# IRIS1304_v2_0.net
KiCad netlist of a schematic drawn in EAGLE
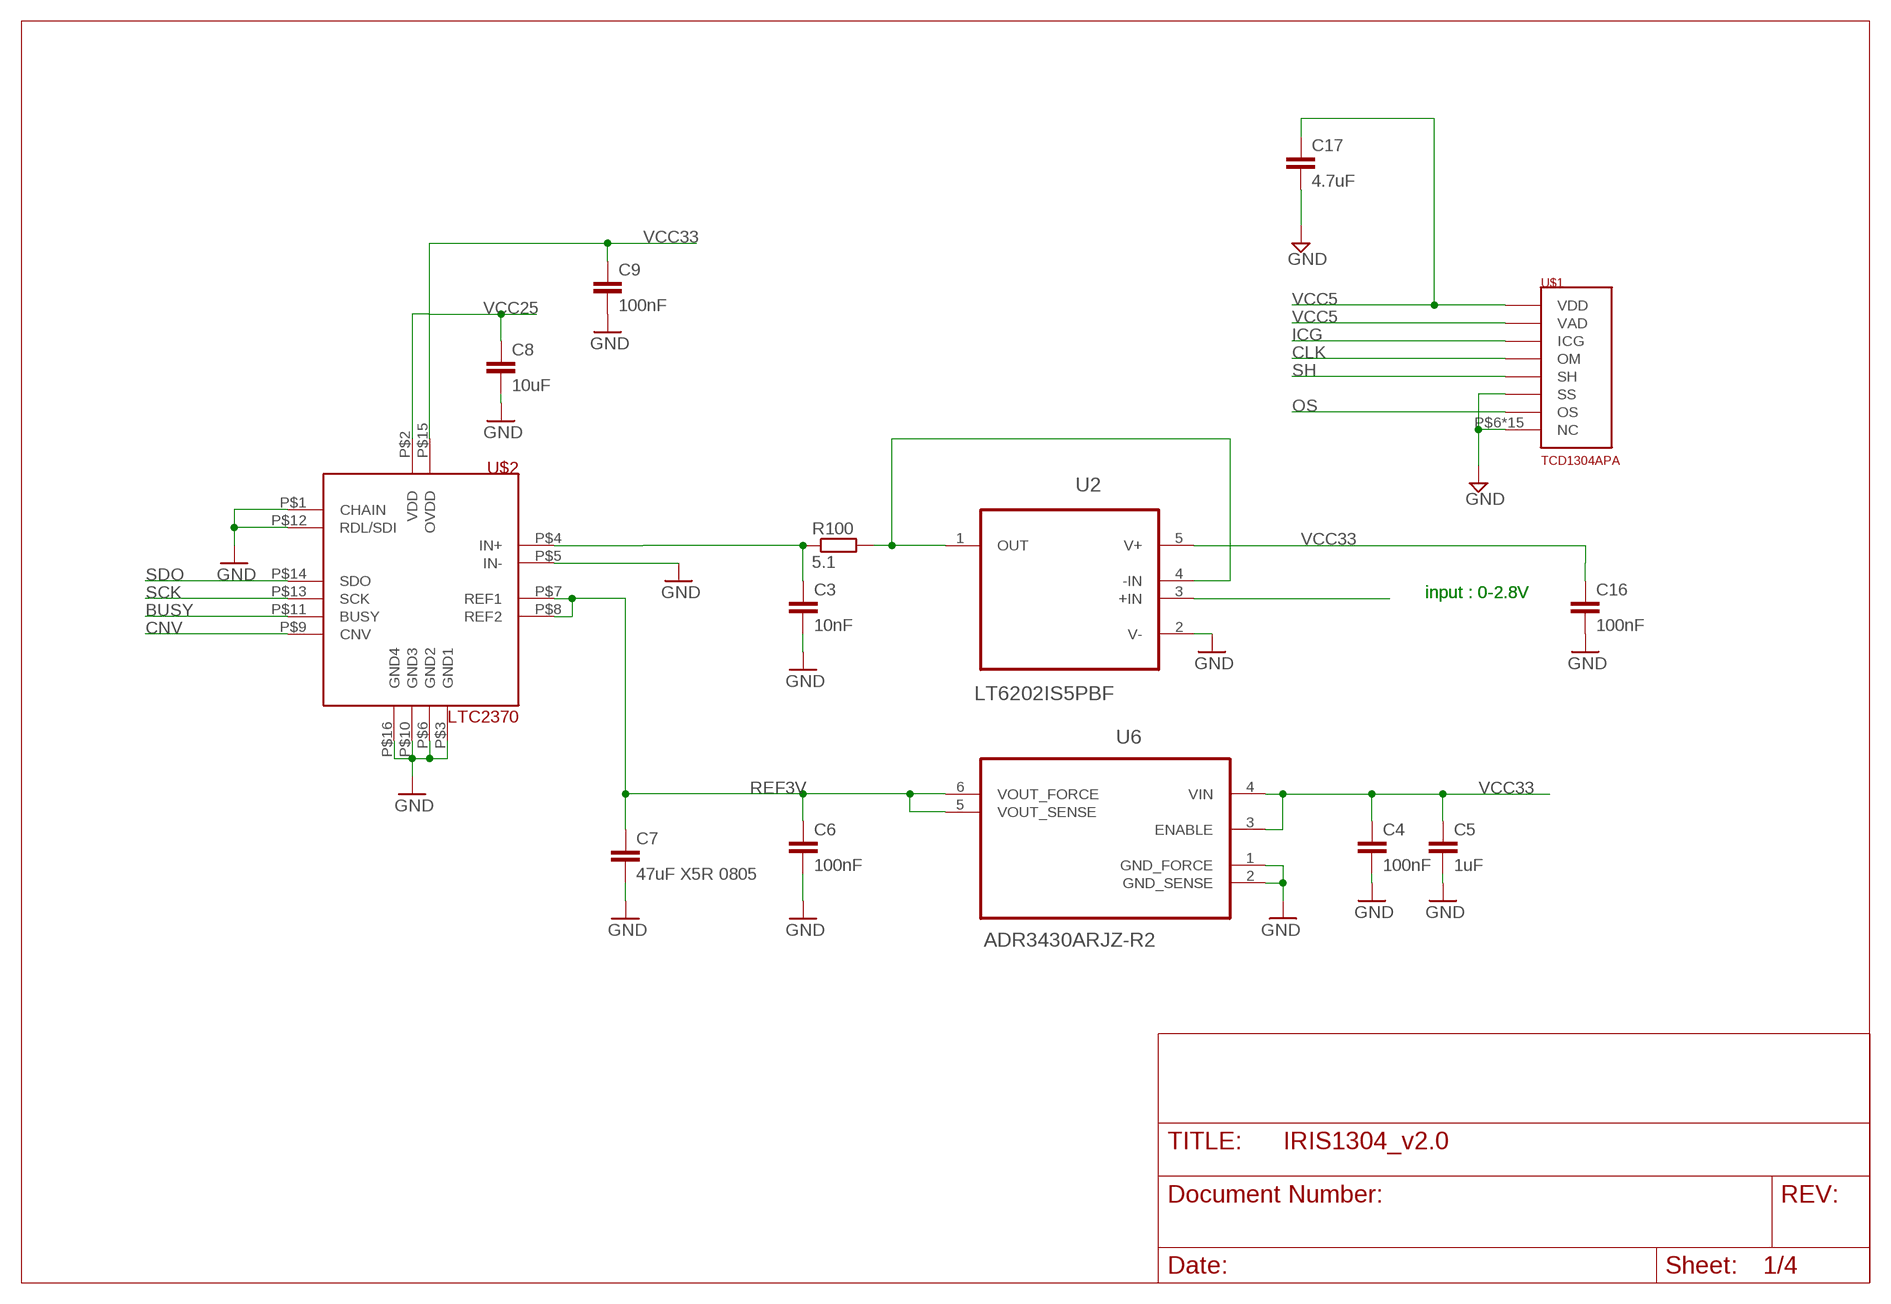
[diagram p0: schematic, sheet 1]
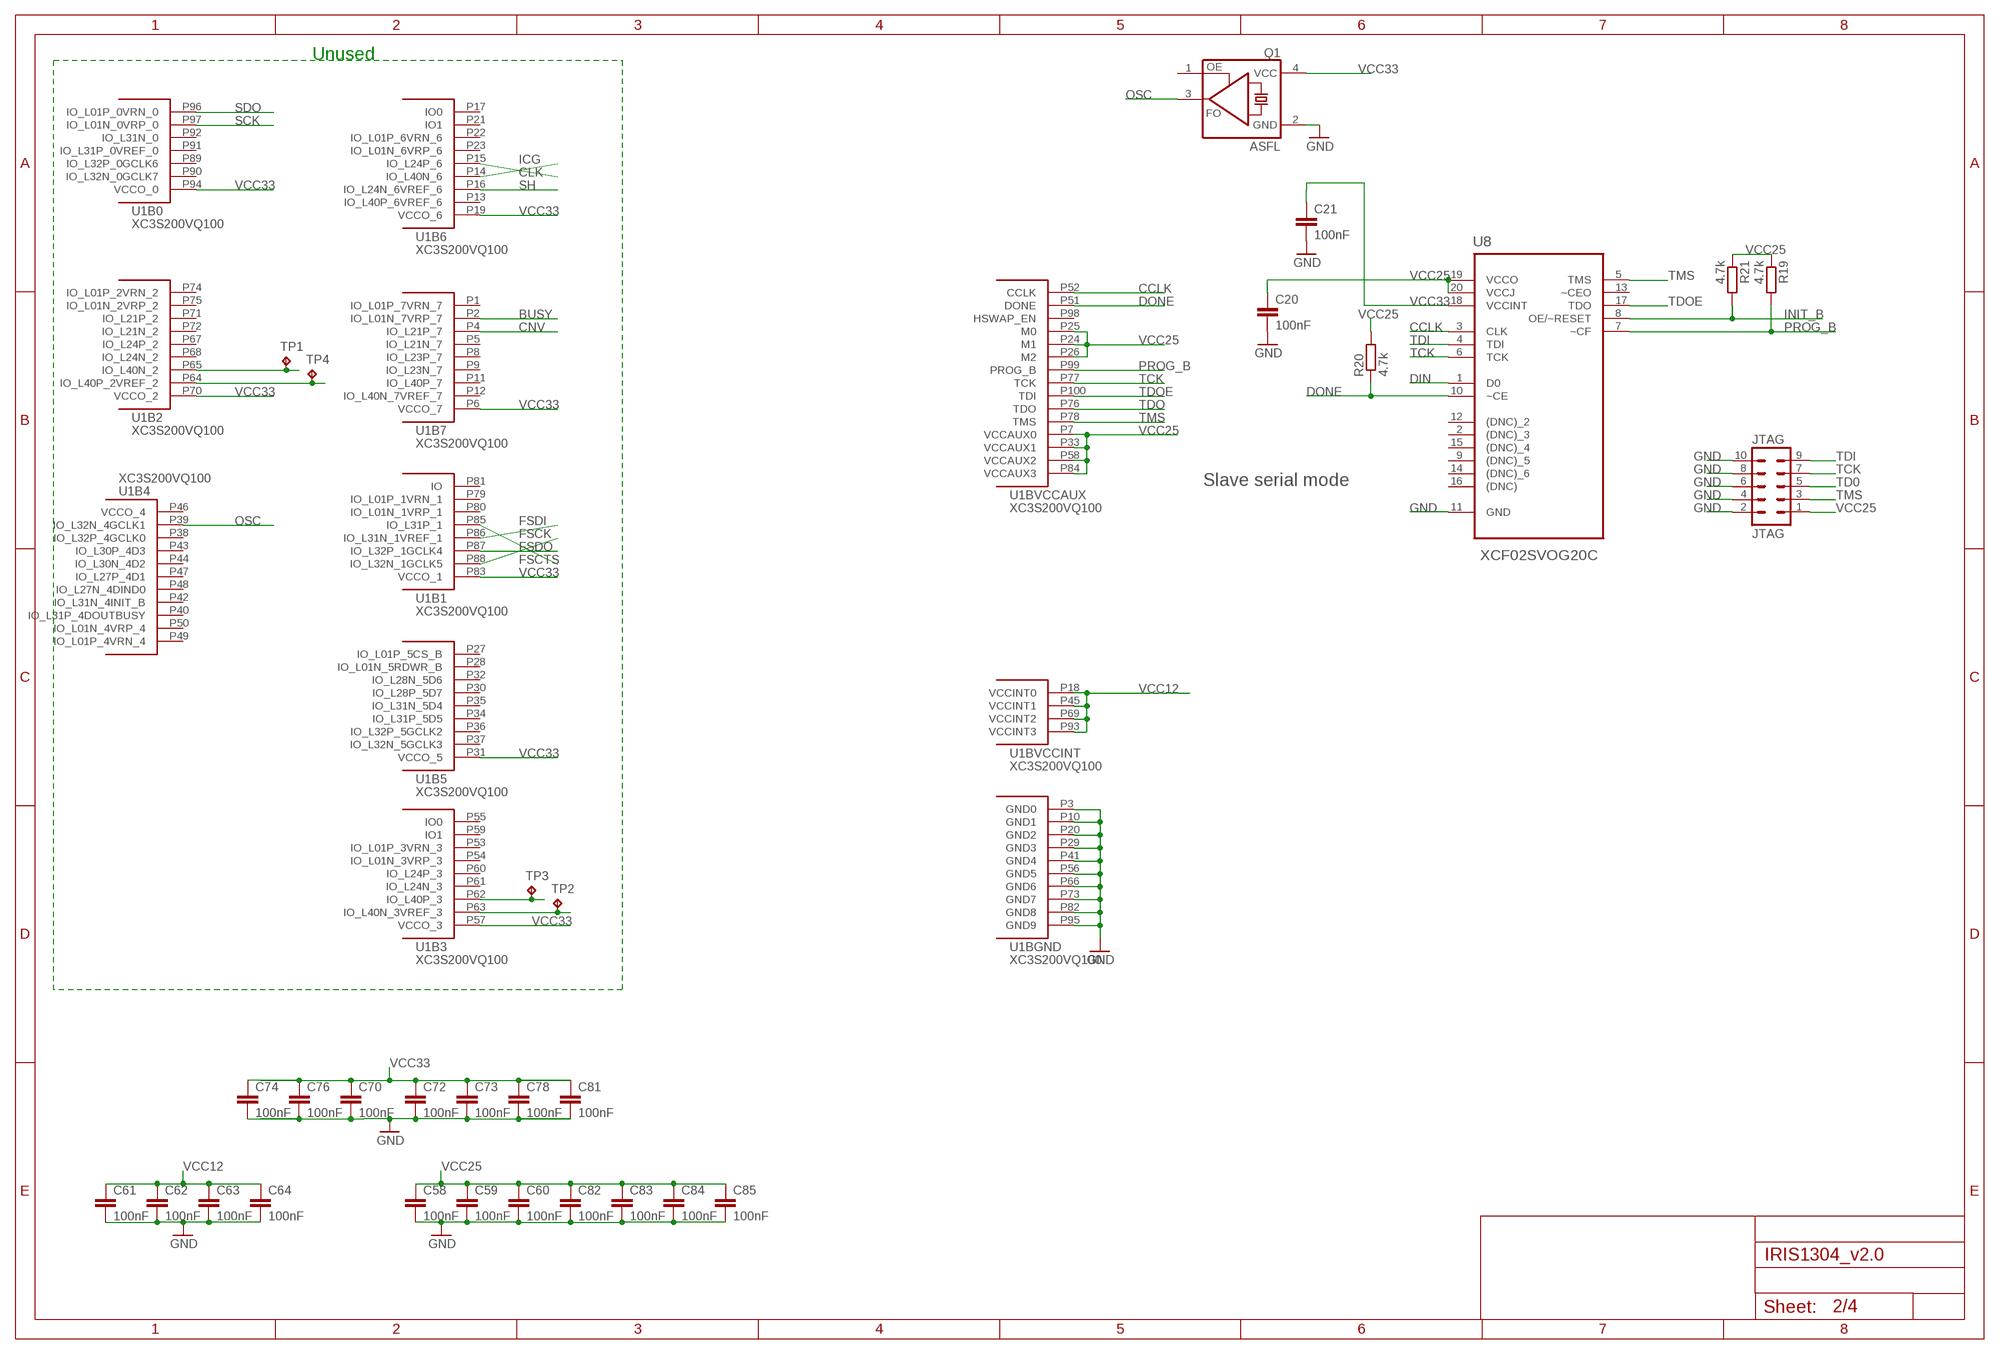
[diagram p1: schematic, sheet 2]
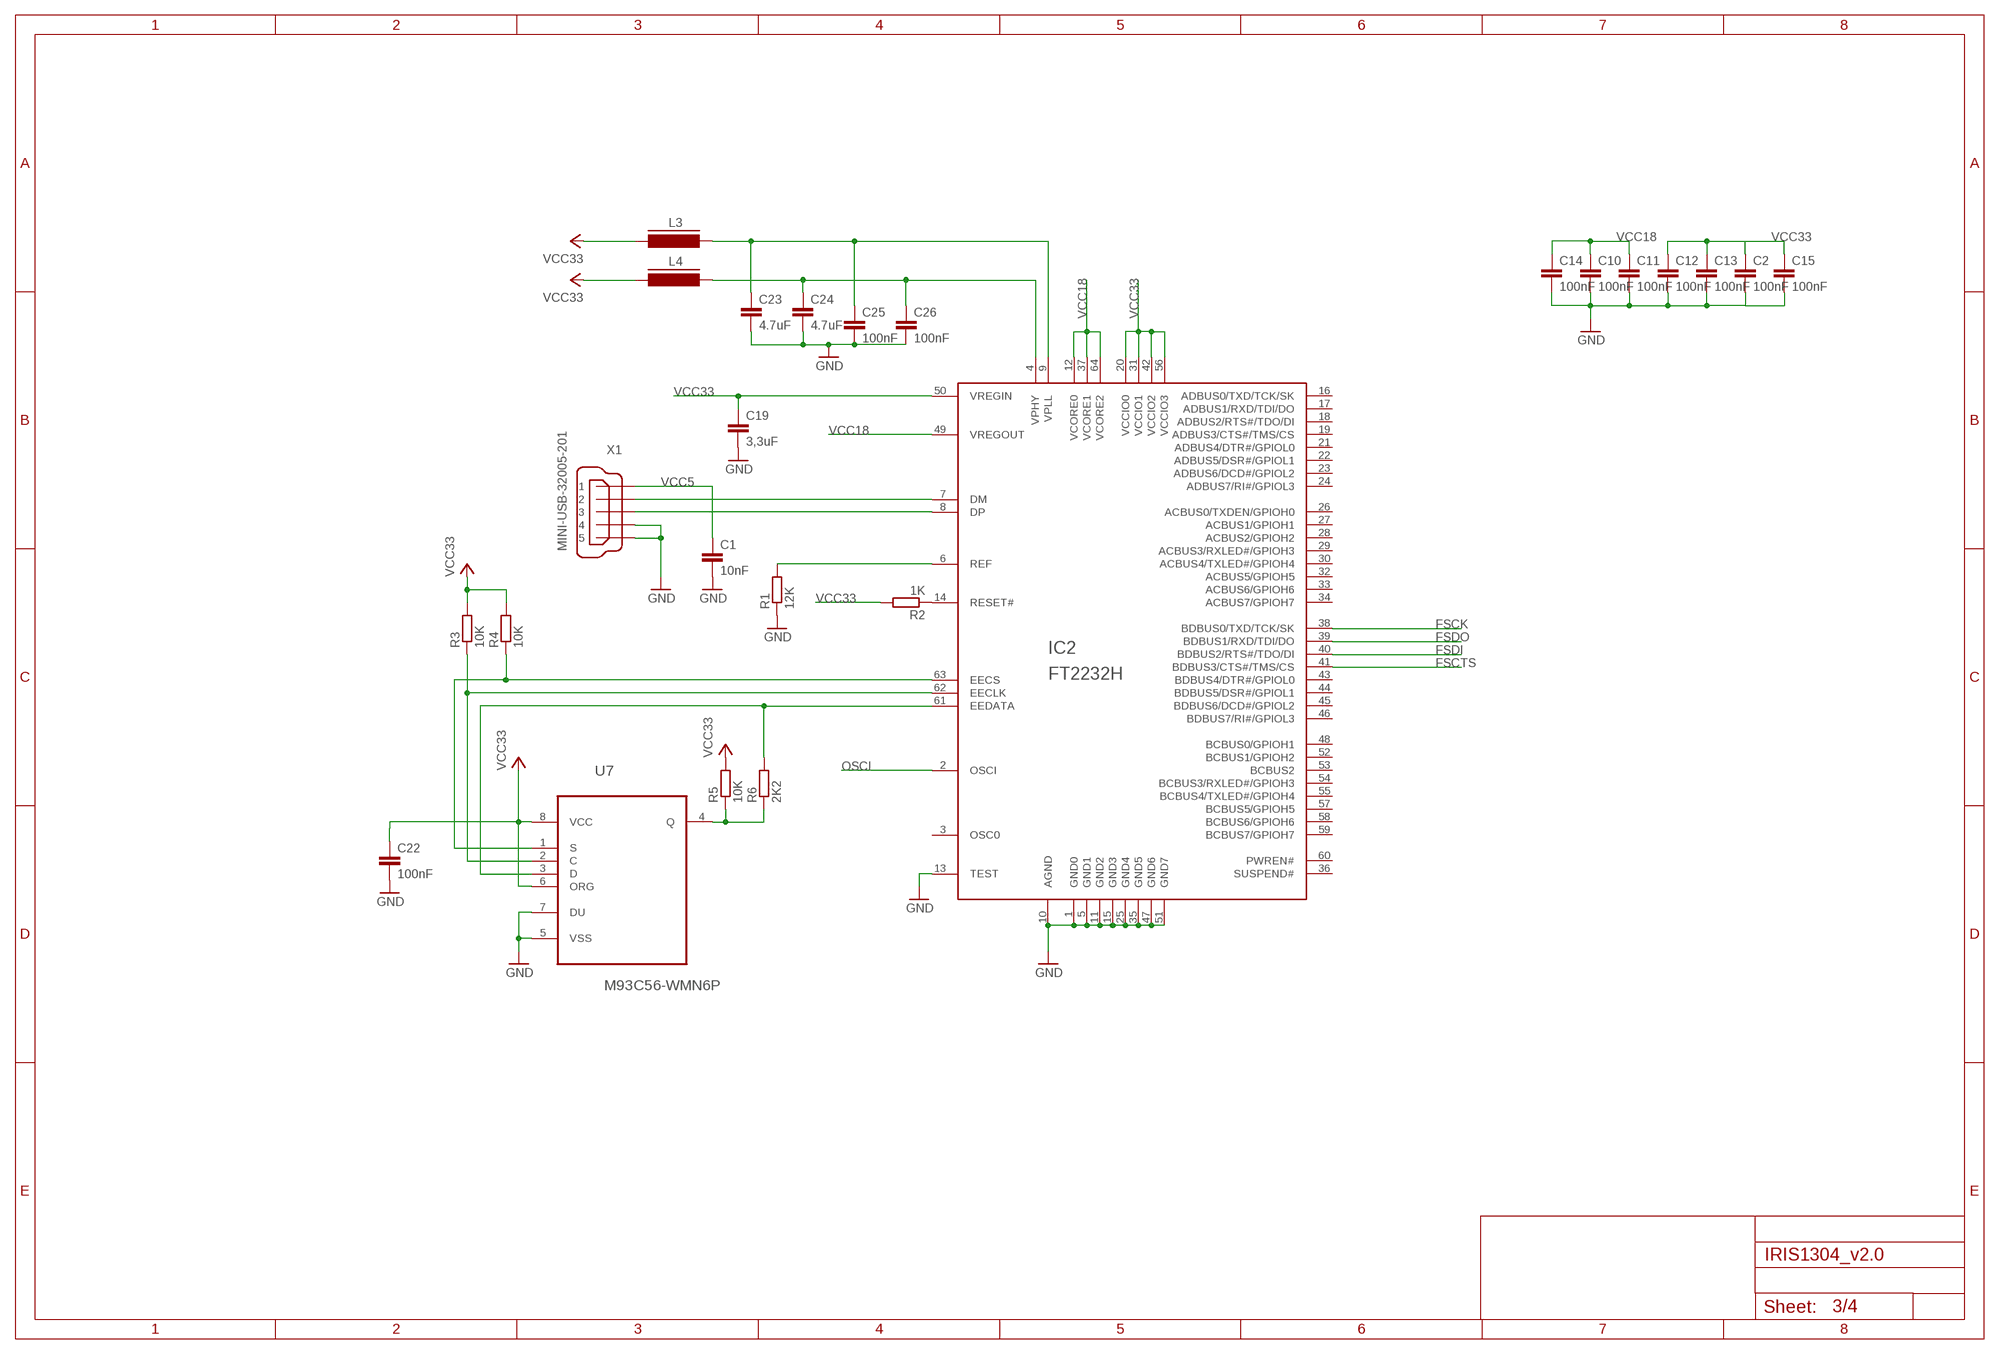
[diagram p2: schematic, sheet 3]
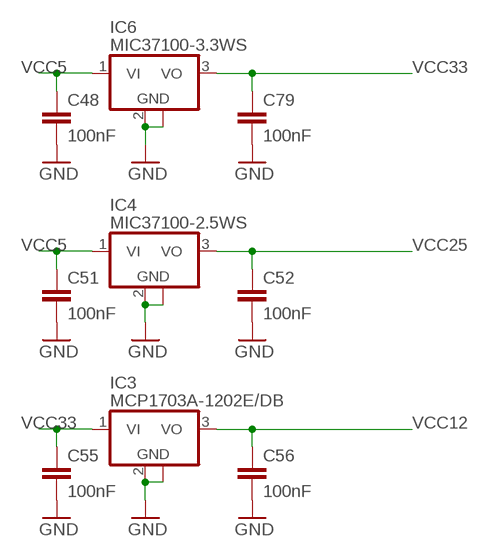
[diagram p3: schematic, sheet 4]

(export (version "E")
  (design (tool "Eeschema 10.0.6"))
  (components
    (comp (ref "C48")
      (value "100nF")
      (footprint "eagle-import:C0603")
      (fields (field (name "MF") "AVX") (field (name "MPN") "06033G104ZAT2A"))
      (libsource (lib "eagle-import") (part "C-EUC0603"))
    )
    (comp (ref "C51")
      (value "100nF")
      (footprint "eagle-import:C0603")
      (fields (field (name "MF") "AVX") (field (name "MPN") "06033G104ZAT2A"))
      (libsource (lib "eagle-import") (part "C-EUC0603"))
    )
    (comp (ref "C52")
      (value "100nF")
      (footprint "eagle-import:C0603")
      (fields (field (name "MF") "AVX") (field (name "MPN") "06033G104ZAT2A"))
      (libsource (lib "eagle-import") (part "C-EUC0603"))
    )
    (comp (ref "C55")
      (value "100nF")
      (footprint "eagle-import:C0603")
      (fields (field (name "MF") "AVX") (field (name "MPN") "06033G104ZAT2A"))
      (libsource (lib "eagle-import") (part "C-EUC0603"))
    )
    (comp (ref "C56")
      (value "100nF")
      (footprint "eagle-import:C0603")
      (fields (field (name "MF") "AVX") (field (name "MPN") "06033G104ZAT2A"))
      (libsource (lib "eagle-import") (part "C-EUC0603"))
    )
    (comp (ref "C79")
      (value "100nF")
      (footprint "eagle-import:C0603")
      (fields (field (name "MF") "AVX") (field (name "MPN") "06033G104ZAT2A"))
      (libsource (lib "eagle-import") (part "C-EUC0603"))
    )
    (comp (ref "IC3")
      (value "MCP1703A-1202E/DB")
      (footprint "eagle-import:SOT223")
      (fields (field (name "MF") "MICROCHIP"))
      (libsource (lib "eagle-import") (part "UA78MDCY05"))
    )
    (comp (ref "IC4")
      (value "MIC37100-2.5WS")
      (footprint "eagle-import:SOT223")
      (fields (field (name "MF") "MICREL SEMICONDUCTOR") (field (name "MPN") "MIC37100-2.5WS TR"))
      (libsource (lib "eagle-import") (part "UA78MDCY05"))
    )
    (comp (ref "IC6")
      (value "MIC37100-3.3WS")
      (footprint "eagle-import:SOT223")
      (fields (field (name "MF") "MICREL SEMICONDUCTOR"))
      (libsource (lib "eagle-import") (part "UA78MDCY05"))
    )
    (comp (ref "C20")
      (value "100nF")
      (footprint "eagle-import:C0603")
      (fields (field (name "MF") "AVX") (field (name "MPN") "06033G104ZAT2A"))
      (libsource (lib "eagle-import") (part "C-EUC0603"))
    )
    (comp (ref "C21")
      (value "100nF")
      (footprint "eagle-import:C0603")
      (fields (field (name "MF") "AVX") (field (name "MPN") "06033G104ZAT2A"))
      (libsource (lib "eagle-import") (part "C-EUC0603"))
    )
    (comp (ref "C58")
      (value "100nF")
      (footprint "eagle-import:C0603")
      (fields (field (name "MF") "AVX") (field (name "MPN") "06033G104ZAT2A"))
      (libsource (lib "eagle-import") (part "C-EUC0603"))
    )
    (comp (ref "C59")
      (value "100nF")
      (footprint "eagle-import:C0603")
      (fields (field (name "MF") "AVX") (field (name "MPN") "06033G104ZAT2A"))
      (libsource (lib "eagle-import") (part "C-EUC0603"))
    )
    (comp (ref "C60")
      (value "100nF")
      (footprint "eagle-import:C0603")
      (fields (field (name "MF") "AVX") (field (name "MPN") "06033G104ZAT2A"))
      (libsource (lib "eagle-import") (part "C-EUC0603"))
    )
    (comp (ref "C61")
      (value "100nF")
      (footprint "eagle-import:C0603")
      (fields (field (name "MF") "AVX") (field (name "MPN") "06033G104ZAT2A"))
      (libsource (lib "eagle-import") (part "C-EUC0603"))
    )
    (comp (ref "C62")
      (value "100nF")
      (footprint "eagle-import:C0603")
      (fields (field (name "MF") "AVX") (field (name "MPN") "06033G104ZAT2A"))
      (libsource (lib "eagle-import") (part "C-EUC0603"))
    )
    (comp (ref "C63")
      (value "100nF")
      (footprint "eagle-import:C0603")
      (fields (field (name "MF") "AVX") (field (name "MPN") "06033G104ZAT2A"))
      (libsource (lib "eagle-import") (part "C-EUC0603"))
    )
    (comp (ref "C64")
      (value "100nF")
      (footprint "eagle-import:C0603")
      (fields (field (name "MF") "AVX") (field (name "MPN") "06033G104ZAT2A"))
      (libsource (lib "eagle-import") (part "C-EUC0603"))
    )
    (comp (ref "C70")
      (value "100nF")
      (footprint "eagle-import:C0603")
      (fields (field (name "MF") "AVX") (field (name "MPN") "06033G104ZAT2A"))
      (libsource (lib "eagle-import") (part "C-EUC0603"))
    )
    (comp (ref "C72")
      (value "100nF")
      (footprint "eagle-import:C0603")
      (fields (field (name "MF") "AVX") (field (name "MPN") "06033G104ZAT2A"))
      (libsource (lib "eagle-import") (part "C-EUC0603"))
    )
    (comp (ref "C73")
      (value "100nF")
      (footprint "eagle-import:C0603")
      (fields (field (name "MF") "AVX") (field (name "MPN") "06033G104ZAT2A"))
      (libsource (lib "eagle-import") (part "C-EUC0603"))
    )
    (comp (ref "C74")
      (value "100nF")
      (footprint "eagle-import:C0603")
      (fields (field (name "MF") "AVX") (field (name "MPN") "06033G104ZAT2A"))
      (libsource (lib "eagle-import") (part "C-EUC0603"))
    )
    (comp (ref "C76")
      (value "100nF")
      (footprint "eagle-import:C0603")
      (fields (field (name "MF") "AVX") (field (name "MPN") "06033G104ZAT2A"))
      (libsource (lib "eagle-import") (part "C-EUC0603"))
    )
    (comp (ref "C78")
      (value "100nF")
      (footprint "eagle-import:C0603")
      (fields (field (name "MF") "AVX") (field (name "MPN") "06033G104ZAT2A"))
      (libsource (lib "eagle-import") (part "C-EUC0603"))
    )
    (comp (ref "C81")
      (value "100nF")
      (footprint "eagle-import:C0603")
      (fields (field (name "MF") "AVX") (field (name "MPN") "06033G104ZAT2A"))
      (libsource (lib "eagle-import") (part "C-EUC0603"))
    )
    (comp (ref "C82")
      (value "100nF")
      (footprint "eagle-import:C0603")
      (fields (field (name "MF") "AVX") (field (name "MPN") "06033G104ZAT2A"))
      (libsource (lib "eagle-import") (part "C-EUC0603"))
    )
    (comp (ref "C83")
      (value "100nF")
      (footprint "eagle-import:C0603")
      (fields (field (name "MF") "AVX") (field (name "MPN") "06033G104ZAT2A"))
      (libsource (lib "eagle-import") (part "C-EUC0603"))
    )
    (comp (ref "C84")
      (value "100nF")
      (footprint "eagle-import:C0603")
      (fields (field (name "MF") "AVX") (field (name "MPN") "06033G104ZAT2A"))
      (libsource (lib "eagle-import") (part "C-EUC0603"))
    )
    (comp (ref "C85")
      (value "100nF")
      (footprint "eagle-import:C0603")
      (fields (field (name "MF") "AVX") (field (name "MPN") "06033G104ZAT2A"))
      (libsource (lib "eagle-import") (part "C-EUC0603"))
    )
    (comp (ref "JTAG")
      (value "JTAG")
      (footprint "eagle-import:ML10")
      (fields
        (field (name "MF") "SAMTEC")
        (field (name "MPN") "TFML-105-01-S-D-RA")
        (field (name "OC_FARNELL") "1801377")
      )
      (libsource (lib "eagle-import") (part "ML10"))
    )
    (comp (ref "Q1")
      (value "ASFL")
      (footprint "eagle-import:ASF")
      (fields
        (field (name "MPN") "ASFLM1-50.000MHZ-C-T")
        (field (name "MF") "ABRACON")
        (field (name "MPN_1") "ASFL1-12.000MHZ-EK-T")
        (field (name "OC_FARNELL") "7943088")
      )
      (libsource (lib "eagle-import") (part "ASFL"))
    )
    (comp (ref "R19")
      (value "4.7k")
      (footprint "eagle-import:R0603")
      (fields (field (name "MF") "VISHAY DRALORIC") (field (name "MPN") "CRCW06034K70FKEA"))
      (libsource (lib "eagle-import") (part "R-EU_R0603"))
    )
    (comp (ref "R20")
      (value "4.7k")
      (footprint "eagle-import:R0603")
      (fields (field (name "MF") "VISHAY DRALORIC") (field (name "MPN") "CRCW06034K70FKEA"))
      (libsource (lib "eagle-import") (part "R-EU_R0603"))
    )
    (comp (ref "R21")
      (value "4.7k")
      (footprint "eagle-import:R0603")
      (fields (field (name "MF") "VISHAY DRALORIC") (field (name "MPN") "CRCW06034K70FKEA"))
      (libsource (lib "eagle-import") (part "R-EU_R0603"))
    )
    (comp (ref "TP1")
      (value "TPB1,27")
      (footprint "eagle-import:B1,27")
      (libsource (lib "eagle-import") (part "TPB1,27"))
    )
    (comp (ref "TP2")
      (value "TPB1,27")
      (footprint "eagle-import:B1,27")
      (libsource (lib "eagle-import") (part "TPB1,27"))
    )
    (comp (ref "TP3")
      (value "TPB1,27")
      (footprint "eagle-import:B1,27")
      (libsource (lib "eagle-import") (part "TPB1,27"))
    )
    (comp (ref "TP4")
      (value "TPB1,27")
      (footprint "eagle-import:B1,27")
      (libsource (lib "eagle-import") (part "TPB1,27"))
    )
    (comp (ref "U1")
      (value "XC3S200VQ100")
      (footprint "eagle-import:VQ100")
      (fields
        (field (name "MF") "XILINX")
        (field (name "MPN") "XC3S200A-4VQG100C")
        (field (name "OC_FARNELL") "1876204")
      )
      (libsource (lib "eagle-import") (part "XC3S200VQ100"))
    )
    (comp (ref "U8")
      (value "XCF02SVOG20C")
      (footprint "eagle-import:SOP65P640X119-20N")
      (fields (field (name "MF") "XILINX"))
      (libsource (lib "eagle-import") (part "XCF02SVOG20C"))
    )
    (comp (ref "C3")
      (value "10nF")
      (footprint "eagle-import:C0603")
      (fields (field (name "MF") "AVX") (field (name "MPN") "06035G103ZAT2A"))
      (libsource (lib "eagle-import") (part "C-EUC0603"))
    )
    (comp (ref "C4")
      (value "100nF")
      (footprint "eagle-import:C0603")
      (fields (field (name "MF") "AVX") (field (name "MPN") "06033G104ZAT2A"))
      (libsource (lib "eagle-import") (part "C-EUC0603"))
    )
    (comp (ref "C5")
      (value "1uF")
      (footprint "eagle-import:C0603")
      (fields (field (name "MF") "KEMET") (field (name "MPN") "C0603C105K3PACTU"))
      (libsource (lib "eagle-import") (part "C-EUC0603"))
    )
    (comp (ref "C6")
      (value "100nF")
      (footprint "eagle-import:C0603")
      (fields (field (name "MF") "AVX") (field (name "MPN") "06033G104ZAT2A"))
      (libsource (lib "eagle-import") (part "C-EUC0603"))
    )
    (comp (ref "C7")
      (value "47uF X5R 0805")
      (footprint "eagle-import:C0805")
      (fields (field (name "MF") "KEMET") (field (name "MPN") "C0805C476M9PACTU"))
      (libsource (lib "eagle-import") (part "C-EUC0805"))
    )
    (comp (ref "C8")
      (value "10uF")
      (footprint "eagle-import:C0603")
      (fields (field (name "MF") "KEMET") (field (name "MPN") "C0603C106M9PACTU"))
      (libsource (lib "eagle-import") (part "C-EUC0603"))
    )
    (comp (ref "C9")
      (value "100nF")
      (footprint "eagle-import:C0603")
      (fields (field (name "MF") "AVX") (field (name "MPN") "06033G104ZAT2A"))
      (libsource (lib "eagle-import") (part "C-EUC0603"))
    )
    (comp (ref "C16")
      (value "100nF")
      (footprint "eagle-import:C0603")
      (fields (field (name "MF") "AVX") (field (name "MPN") "06033G104ZAT2A"))
      (libsource (lib "eagle-import") (part "C-EUC0603"))
    )
    (comp (ref "C17")
      (value "4.7uF")
      (footprint "eagle-import:C0603")
      (fields (field (name "MF") "YAGEO (PHYCOMP)") (field (name "MPN") "CC0603KRX5R6BB475"))
      (libsource (lib "eagle-import") (part "C-EUC0603"))
    )
    (comp (ref "R100")
      (value "5.1")
      (footprint "eagle-import:R0603")
      (fields (field (name "MF") "VISHAY DALE") (field (name "MPN") "CRCW06035R10FNEA"))
      (libsource (lib "eagle-import") (part "R-EU_R0603"))
    )
    (comp (ref "U$1")
      (value "TCD1304APA")
      (footprint "eagle-import:ILX511")
      (libsource (lib "eagle-import") (part "TCD1304APA"))
    )
    (comp (ref "U$2")
      (value "LTC2370")
      (footprint "eagle-import:MSOP-16")
      (fields (field (name "MF") "LINEAR TECHNOLOGY") (field (name "MPN") "LTC2370CMS-16"))
      (libsource (lib "eagle-import") (part "LTC2370"))
    )
    (comp (ref "U2")
      (value "LT6202IS5PBF")
      (footprint "eagle-import:SOT95P280X100-5N")
      (fields (field (name "MPN") "LT6202IS5#PBF") (field (name "MF") "LINEAR TECHNOLOGY"))
      (libsource (lib "eagle-import") (part "LT6202IS5PBF"))
    )
    (comp (ref "U6")
      (value "ADR3430ARJZ-R2")
      (footprint "eagle-import:SOT95P280X145-6N")
      (fields (field (name "MF") "ANALOG DEVICES"))
      (libsource (lib "eagle-import") (part "ADR3430ARJZ-R2"))
    )
    (comp (ref "C1")
      (value "10nF")
      (footprint "eagle-import:C0603")
      (fields (field (name "MF") "AVX") (field (name "MPN") "06035G103ZAT2A"))
      (libsource (lib "eagle-import") (part "C-EUC0603"))
    )
    (comp (ref "C2")
      (value "100nF")
      (footprint "eagle-import:C0603")
      (fields (field (name "MF") "AVX") (field (name "MPN") "06033G104ZAT2A"))
      (libsource (lib "eagle-import") (part "C-EUC0603"))
    )
    (comp (ref "C10")
      (value "100nF")
      (footprint "eagle-import:C0603")
      (fields (field (name "MF") "AVX") (field (name "MPN") "06033G104ZAT2A"))
      (libsource (lib "eagle-import") (part "C-EUC0603"))
    )
    (comp (ref "C11")
      (value "100nF")
      (footprint "eagle-import:C0603")
      (fields (field (name "MF") "AVX") (field (name "MPN") "06033G104ZAT2A"))
      (libsource (lib "eagle-import") (part "C-EUC0603"))
    )
    (comp (ref "C12")
      (value "100nF")
      (footprint "eagle-import:C0603")
      (fields (field (name "MF") "AVX") (field (name "MPN") "06033G104ZAT2A"))
      (libsource (lib "eagle-import") (part "C-EUC0603"))
    )
    (comp (ref "C13")
      (value "100nF")
      (footprint "eagle-import:C0603")
      (fields (field (name "MF") "AVX") (field (name "MPN") "06033G104ZAT2A"))
      (libsource (lib "eagle-import") (part "C-EUC0603"))
    )
    (comp (ref "C14")
      (value "100nF")
      (footprint "eagle-import:C0603")
      (fields (field (name "MF") "AVX") (field (name "MPN") "06033G104ZAT2A"))
      (libsource (lib "eagle-import") (part "C-EUC0603"))
    )
    (comp (ref "C15")
      (value "100nF")
      (footprint "eagle-import:C0603")
      (fields (field (name "MF") "AVX") (field (name "MPN") "06033G104ZAT2A"))
      (libsource (lib "eagle-import") (part "C-EUC0603"))
    )
    (comp (ref "C19")
      (value "3,3uF")
      (footprint "eagle-import:C0805")
      (fields (field (name "MF") "AVX") (field (name "MPN") "0805ZD335KAT2A"))
      (libsource (lib "eagle-import") (part "C-EUC0805"))
    )
    (comp (ref "C22")
      (value "100nF")
      (footprint "eagle-import:C0603")
      (fields (field (name "MF") "AVX") (field (name "MPN") "06033G104ZAT2A"))
      (libsource (lib "eagle-import") (part "C-EUC0603"))
    )
    (comp (ref "C23")
      (value "4.7uF")
      (footprint "eagle-import:C0603")
      (fields (field (name "MF") "YAGEO (PHYCOMP)") (field (name "MPN") "CC0603KRX5R6BB475"))
      (libsource (lib "eagle-import") (part "C-EUC0603"))
    )
    (comp (ref "C24")
      (value "4.7uF")
      (footprint "eagle-import:C0603")
      (fields (field (name "MF") "YAGEO (PHYCOMP)") (field (name "MPN") "CC0603KRX5R6BB475"))
      (libsource (lib "eagle-import") (part "C-EUC0603"))
    )
    (comp (ref "C25")
      (value "100nF")
      (footprint "eagle-import:C0603")
      (fields (field (name "MF") "AVX") (field (name "MPN") "06033G104ZAT2A"))
      (libsource (lib "eagle-import") (part "C-EUC0603"))
    )
    (comp (ref "C26")
      (value "100nF")
      (footprint "eagle-import:C0603")
      (fields (field (name "MF") "AVX") (field (name "MPN") "06033G104ZAT2A"))
      (libsource (lib "eagle-import") (part "C-EUC0603"))
    )
    (comp (ref "IC2")
      (value "FT2232H")
      (footprint "eagle-import:LQFP64")
      (fields (field (name "MF") "FTDI") (field (name "MPN") "FT2232HL-R"))
      (libsource (lib "eagle-import") (part "FT2232H"))
    )
    (comp (ref "L3")
      (value "FERRITE_BEAD805")
      (footprint "eagle-import:FB805")
      (libsource (lib "eagle-import") (part "FERRITE_BEAD805"))
    )
    (comp (ref "L4")
      (value "FERRITE_BEAD805")
      (footprint "eagle-import:FB805")
      (libsource (lib "eagle-import") (part "FERRITE_BEAD805"))
    )
    (comp (ref "R1")
      (value "12K")
      (footprint "eagle-import:R0603")
      (fields (field (name "MF") "TE CONNECTIVITY") (field (name "MPN") "CPF0201D12K1C1"))
      (libsource (lib "eagle-import") (part "R-EU_R0603"))
    )
    (comp (ref "R2")
      (value "1K")
      (footprint "eagle-import:R0603")
      (fields (field (name "MF") "VISHAY DRALORIC") (field (name "MPN") "CRCW06031K00FKEA"))
      (libsource (lib "eagle-import") (part "R-EU_R0603"))
    )
    (comp (ref "R3")
      (value "10K")
      (footprint "eagle-import:R0603")
      (fields (field (name "MF") "TE CONNECTIVITY / NEOHM") (field (name "MPN") "CPF0603F10KC1"))
      (libsource (lib "eagle-import") (part "R-EU_R0603"))
    )
    (comp (ref "R4")
      (value "10K")
      (footprint "eagle-import:R0603")
      (fields (field (name "MF") "TE CONNECTIVITY / NEOHM") (field (name "MPN") "CPF0603F10KC1"))
      (libsource (lib "eagle-import") (part "R-EU_R0603"))
    )
    (comp (ref "R5")
      (value "10K")
      (footprint "eagle-import:R0603")
      (fields (field (name "MF") "TE CONNECTIVITY / NEOHM") (field (name "MPN") "CPF0603F10KC1"))
      (libsource (lib "eagle-import") (part "R-EU_R0603"))
    )
    (comp (ref "R6")
      (value "2K2")
      (footprint "eagle-import:R0603")
      (fields (field (name "MF") "PANASONIC") (field (name "MPN") "ERJP03F2201V"))
      (libsource (lib "eagle-import") (part "R-EU_R0603"))
    )
    (comp (ref "U7")
      (value "M93C56-WMN6P")
      (footprint "eagle-import:SOIC127P600X175-8N")
      (fields (field (name "MF") "STMICROELECTRONICS"))
      (libsource (lib "eagle-import") (part "M93C56-WMN6P"))
    )
    (comp (ref "X1")
      (value "MINI-USB-32005-201")
      (footprint "eagle-import:32005-201")
      (fields
        (field (name "MF") "WURTH ELEKTRONIK")
        (field (name "MPN") "65100516121")
        (field (name "OC_FARNELL") "1642036")
      )
      (libsource (lib "eagle-import") (part "MINI-USB-32005-201"))
    )
  )
  (nets
    (net (code "1") (name "BUSY") (class "Default")
      (node (ref "U$2") (pin "P$11") (pinfunction "BUSY_P$11") (pintype "bidirectional"))
      (node (ref "U1") (pin "P2") (pinfunction "IO_L01N_7VRP_7_P2") (pintype "bidirectional"))
    )
    (net (code "2") (name "CCLK") (class "Default")
      (node (ref "U1") (pin "P52") (pinfunction "CCLK_P52") (pintype "bidirectional"))
      (node (ref "U8") (pin "3") (pinfunction "CLK_3") (pintype "input"))
    )
    (net (code "3") (name "CLK") (class "Default")
      (node (ref "U$1") (pin "P$4") (pinfunction "OM_P$4") (pintype "bidirectional"))
      (node (ref "U1") (pin "P15") (pinfunction "IO_L24P_6_P15") (pintype "bidirectional"))
    )
    (net (code "4") (name "CNV") (class "Default")
      (node (ref "U$2") (pin "P$9") (pinfunction "CNV_P$9") (pintype "bidirectional"))
      (node (ref "U1") (pin "P4") (pinfunction "IO_L21P_7_P4") (pintype "bidirectional"))
    )
    (net (code "5") (name "DIN") (class "Default")
      (node (ref "U8") (pin "1") (pinfunction "D0_1") (pintype "input"))
    )
    (net (code "6") (name "DONE") (class "Default")
      (node (ref "R20") (pin "1") (pinfunction "1_1") (pintype "passive"))
      (node (ref "U1") (pin "P51") (pinfunction "DONE_P51") (pintype "bidirectional"))
      (node (ref "U8") (pin "10") (pinfunction "~{CE}_10") (pintype "input"))
    )
    (net (code "7") (name "FSCK") (class "Default")
      (node (ref "IC2") (pin "38") (pinfunction "BDBUS0/TXD/TCK/SK_38") (pintype "bidirectional"))
      (node (ref "U1") (pin "P88") (pinfunction "IO_L32N_1GCLK5_P88") (pintype "bidirectional"))
    )
    (net (code "8") (name "FSCTS") (class "Default")
      (node (ref "IC2") (pin "41") (pinfunction "BDBUS3/CTS#/TMS/CS_41") (pintype "bidirectional"))
      (node (ref "U1") (pin "P85") (pinfunction "IO_L31P_1_P85") (pintype "bidirectional"))
    )
    (net (code "9") (name "FSDI") (class "Default")
      (node (ref "IC2") (pin "40") (pinfunction "BDBUS2/RTS#/TDO/DI_40") (pintype "bidirectional"))
      (node (ref "U1") (pin "P86") (pinfunction "IO_L31N_1VREF_1_P86") (pintype "bidirectional"))
    )
    (net (code "10") (name "FSDO") (class "Default")
      (node (ref "IC2") (pin "39") (pinfunction "BDBUS1/RXD/TDI/DO_39") (pintype "bidirectional"))
      (node (ref "U1") (pin "P87") (pinfunction "IO_L32P_1GCLK4_P87") (pintype "bidirectional"))
    )
    (net (code "11") (name "GND") (class "Default")
      (node (ref "C1") (pin "2") (pinfunction "2_2") (pintype "passive"))
      (node (ref "C10") (pin "2") (pinfunction "2_2") (pintype "passive"))
      (node (ref "C11") (pin "2") (pinfunction "2_2") (pintype "passive"))
      (node (ref "C12") (pin "2") (pinfunction "2_2") (pintype "passive"))
      (node (ref "C13") (pin "2") (pinfunction "2_2") (pintype "passive"))
      (node (ref "C14") (pin "2") (pinfunction "2_2") (pintype "passive"))
      (node (ref "C15") (pin "2") (pinfunction "2_2") (pintype "passive"))
      (node (ref "C16") (pin "2") (pinfunction "2_2") (pintype "passive"))
      (node (ref "C17") (pin "2") (pinfunction "2_2") (pintype "passive"))
      (node (ref "C19") (pin "2") (pinfunction "2_2") (pintype "passive"))
      (node (ref "C2") (pin "2") (pinfunction "2_2") (pintype "passive"))
      (node (ref "C20") (pin "2") (pinfunction "2_2") (pintype "passive"))
      (node (ref "C21") (pin "2") (pinfunction "2_2") (pintype "passive"))
      (node (ref "C22") (pin "2") (pinfunction "2_2") (pintype "passive"))
      (node (ref "C23") (pin "2") (pinfunction "2_2") (pintype "passive"))
      (node (ref "C24") (pin "2") (pinfunction "2_2") (pintype "passive"))
      (node (ref "C25") (pin "2") (pinfunction "2_2") (pintype "passive"))
      (node (ref "C26") (pin "2") (pinfunction "2_2") (pintype "passive"))
      (node (ref "C3") (pin "2") (pinfunction "2_2") (pintype "passive"))
      (node (ref "C4") (pin "2") (pinfunction "2_2") (pintype "passive"))
      (node (ref "C48") (pin "2") (pinfunction "2_2") (pintype "passive"))
      (node (ref "C5") (pin "2") (pinfunction "2_2") (pintype "passive"))
      (node (ref "C51") (pin "2") (pinfunction "2_2") (pintype "passive"))
      (node (ref "C52") (pin "2") (pinfunction "2_2") (pintype "passive"))
      (node (ref "C55") (pin "2") (pinfunction "2_2") (pintype "passive"))
      (node (ref "C56") (pin "2") (pinfunction "2_2") (pintype "passive"))
      (node (ref "C58") (pin "2") (pinfunction "2_2") (pintype "passive"))
      (node (ref "C59") (pin "2") (pinfunction "2_2") (pintype "passive"))
      (node (ref "C6") (pin "2") (pinfunction "2_2") (pintype "passive"))
      (node (ref "C60") (pin "2") (pinfunction "2_2") (pintype "passive"))
      (node (ref "C61") (pin "2") (pinfunction "2_2") (pintype "passive"))
      (node (ref "C62") (pin "2") (pinfunction "2_2") (pintype "passive"))
      (node (ref "C63") (pin "2") (pinfunction "2_2") (pintype "passive"))
      (node (ref "C64") (pin "2") (pinfunction "2_2") (pintype "passive"))
      (node (ref "C7") (pin "2") (pinfunction "2_2") (pintype "passive"))
      (node (ref "C70") (pin "2") (pinfunction "2_2") (pintype "passive"))
      (node (ref "C72") (pin "2") (pinfunction "2_2") (pintype "passive"))
      (node (ref "C73") (pin "2") (pinfunction "2_2") (pintype "passive"))
      (node (ref "C74") (pin "2") (pinfunction "2_2") (pintype "passive"))
      (node (ref "C76") (pin "2") (pinfunction "2_2") (pintype "passive"))
      (node (ref "C78") (pin "2") (pinfunction "2_2") (pintype "passive"))
      (node (ref "C79") (pin "2") (pinfunction "2_2") (pintype "passive"))
      (node (ref "C8") (pin "2") (pinfunction "2_2") (pintype "passive"))
      (node (ref "C81") (pin "2") (pinfunction "2_2") (pintype "passive"))
      (node (ref "C82") (pin "2") (pinfunction "2_2") (pintype "passive"))
      (node (ref "C83") (pin "2") (pinfunction "2_2") (pintype "passive"))
      (node (ref "C84") (pin "2") (pinfunction "2_2") (pintype "passive"))
      (node (ref "C85") (pin "2") (pinfunction "2_2") (pintype "passive"))
      (node (ref "C9") (pin "2") (pinfunction "2_2") (pintype "passive"))
      (node (ref "IC2") (pin "1") (pinfunction "GND0_1") (pintype "bidirectional"))
      (node (ref "IC2") (pin "10") (pinfunction "AGND_10") (pintype "bidirectional"))
      (node (ref "IC2") (pin "11") (pinfunction "GND2_11") (pintype "bidirectional"))
      (node (ref "IC2") (pin "13") (pinfunction "TEST_13") (pintype "bidirectional"))
      (node (ref "IC2") (pin "15") (pinfunction "GND3_15") (pintype "bidirectional"))
      (node (ref "IC2") (pin "25") (pinfunction "GND4_25") (pintype "bidirectional"))
      (node (ref "IC2") (pin "35") (pinfunction "GND5_35") (pintype "bidirectional"))
      (node (ref "IC2") (pin "47") (pinfunction "GND6_47") (pintype "bidirectional"))
      (node (ref "IC2") (pin "5") (pinfunction "GND1_5") (pintype "bidirectional"))
      (node (ref "IC2") (pin "51") (pinfunction "GND7_51") (pintype "bidirectional"))
      (node (ref "IC3") (pin "2") (pinfunction "GND_2") (pintype "passive"))
      (node (ref "IC3") (pin "4") (pinfunction "GND_4") (pintype "passive"))
      (node (ref "IC4") (pin "2") (pinfunction "GND_2") (pintype "passive"))
      (node (ref "IC4") (pin "4") (pinfunction "GND_4") (pintype "passive"))
      (node (ref "IC6") (pin "2") (pinfunction "GND_2") (pintype "passive"))
      (node (ref "IC6") (pin "4") (pinfunction "GND_4") (pintype "passive"))
      (node (ref "JTAG") (pin "10") (pinfunction "10_10") (pintype "passive"))
      (node (ref "JTAG") (pin "2") (pinfunction "2_2") (pintype "passive"))
      (node (ref "JTAG") (pin "4") (pinfunction "4_4") (pintype "passive"))
      (node (ref "JTAG") (pin "6") (pinfunction "6_6") (pintype "passive"))
      (node (ref "JTAG") (pin "8") (pinfunction "8_8") (pintype "passive"))
      (node (ref "Q1") (pin "2") (pinfunction "GND_2") (pintype "power_in"))
      (node (ref "R1") (pin "1") (pinfunction "1_1") (pintype "passive"))
      (node (ref "U$1") (pin "P$10") (pinfunction "NC_P$10") (pintype "bidirectional"))
      (node (ref "U$1") (pin "P$11") (pinfunction "NC_P$11") (pintype "bidirectional"))
      (node (ref "U$1") (pin "P$12") (pinfunction "NC_P$12") (pintype "bidirectional"))
      (node (ref "U$1") (pin "P$13") (pinfunction "NC_P$13") (pintype "bidirectional"))
      (node (ref "U$1") (pin "P$14") (pinfunction "NC_P$14") (pintype "bidirectional"))
      (node (ref "U$1") (pin "P$15") (pinfunction "NC_P$15") (pintype "bidirectional"))
      (node (ref "U$1") (pin "P$16") (pinfunction "NC_P$16") (pintype "bidirectional"))
      (node (ref "U$1") (pin "P$17") (pinfunction "NC_P$17") (pintype "bidirectional"))
      (node (ref "U$1") (pin "P$18") (pinfunction "NC_P$18") (pintype "bidirectional"))
      (node (ref "U$1") (pin "P$19") (pinfunction "NC_P$19") (pintype "bidirectional"))
      (node (ref "U$1") (pin "P$20") (pinfunction "NC_P$20") (pintype "bidirectional"))
      (node (ref "U$1") (pin "P$22") (pinfunction "SS_P$22") (pintype "bidirectional"))
      (node (ref "U$1") (pin "P$6") (pinfunction "NC_P$6") (pintype "bidirectional"))
      (node (ref "U$1") (pin "P$7") (pinfunction "NC_P$7") (pintype "bidirectional"))
      (node (ref "U$1") (pin "P$8") (pinfunction "NC_P$8") (pintype "bidirectional"))
      (node (ref "U$1") (pin "P$9") (pinfunction "NC_P$9") (pintype "bidirectional"))
      (node (ref "U$2") (pin "P$1") (pinfunction "CHAIN_P$1") (pintype "bidirectional"))
      (node (ref "U$2") (pin "P$10") (pinfunction "GND3_P$10") (pintype "bidirectional"))
      (node (ref "U$2") (pin "P$12") (pinfunction "RDL/SDI_P$12") (pintype "bidirectional"))
      (node (ref "U$2") (pin "P$16") (pinfunction "GND4_P$16") (pintype "bidirectional"))
      (node (ref "U$2") (pin "P$3") (pinfunction "GND1_P$3") (pintype "bidirectional"))
      (node (ref "U$2") (pin "P$5") (pinfunction "IN-_P$5") (pintype "bidirectional"))
      (node (ref "U$2") (pin "P$6") (pinfunction "GND2_P$6") (pintype "bidirectional"))
      (node (ref "U1") (pin "P10") (pinfunction "GND1_P10") (pintype "passive"))
      (node (ref "U1") (pin "P20") (pinfunction "GND2_P20") (pintype "passive"))
      (node (ref "U1") (pin "P29") (pinfunction "GND3_P29") (pintype "passive"))
      (node (ref "U1") (pin "P3") (pinfunction "GND0_P3") (pintype "passive"))
      (node (ref "U1") (pin "P41") (pinfunction "GND4_P41") (pintype "passive"))
      (node (ref "U1") (pin "P56") (pinfunction "GND5_P56") (pintype "passive"))
      (node (ref "U1") (pin "P66") (pinfunction "GND6_P66") (pintype "passive"))
      (node (ref "U1") (pin "P73") (pinfunction "GND7_P73") (pintype "passive"))
      (node (ref "U1") (pin "P82") (pinfunction "GND8_P82") (pintype "passive"))
      (node (ref "U1") (pin "P95") (pinfunction "GND9_P95") (pintype "passive"))
      (node (ref "U2") (pin "2") (pinfunction "V-_2") (pintype "power_in"))
      (node (ref "U6") (pin "1") (pinfunction "GND_FORCE_1") (pintype "passive"))
      (node (ref "U6") (pin "2") (pinfunction "GND_SENSE_2") (pintype "passive"))
      (node (ref "U7") (pin "5") (pinfunction "VSS_5") (pintype "power_in"))
      (node (ref "U7") (pin "7") (pinfunction "DU_7") (pintype "input"))
      (node (ref "U8") (pin "11") (pinfunction "GND_11") (pintype "passive"))
      (node (ref "X1") (pin "4") (pinfunction "4_4") (pintype "passive"))
      (node (ref "X1") (pin "5") (pinfunction "5_5") (pintype "passive"))
    )
    (net (code "12") (name "ICG") (class "Default")
      (node (ref "U$1") (pin "P$3") (pinfunction "ICG_P$3") (pintype "bidirectional"))
      (node (ref "U1") (pin "P14") (pinfunction "IO_L40N_6_P14") (pintype "bidirectional"))
    )
    (net (code "13") (name "INIT_B") (class "Default")
      (node (ref "R21") (pin "2") (pinfunction "2_2") (pintype "passive"))
      (node (ref "U8") (pin "8") (pinfunction "OE/~{RESET}_8") (pintype "bidirectional"))
    )
    (net (code "14") (name "Net-(IC2-DM)") (class "Default")
      (node (ref "IC2") (pin "7") (pinfunction "DM_7") (pintype "bidirectional"))
      (node (ref "X1") (pin "2") (pinfunction "2_2") (pintype "passive"))
    )
    (net (code "15") (name "Net-(IC2-DP)") (class "Default")
      (node (ref "IC2") (pin "8") (pinfunction "DP_8") (pintype "bidirectional"))
      (node (ref "X1") (pin "3") (pinfunction "3_3") (pintype "passive"))
    )
    (net (code "16") (name "Net-(IC2-EECLK)") (class "Default")
      (node (ref "IC2") (pin "62") (pinfunction "EECLK_62") (pintype "bidirectional"))
      (node (ref "R3") (pin "1") (pinfunction "1_1") (pintype "passive"))
      (node (ref "U7") (pin "2") (pinfunction "C_2") (pintype "input"))
    )
    (net (code "17") (name "Net-(IC2-EECS)") (class "Default")
      (node (ref "IC2") (pin "63") (pinfunction "EECS_63") (pintype "bidirectional"))
      (node (ref "R4") (pin "1") (pinfunction "1_1") (pintype "passive"))
      (node (ref "U7") (pin "1") (pinfunction "S_1") (pintype "input"))
    )
    (net (code "18") (name "Net-(IC2-EEDATA)") (class "Default")
      (node (ref "IC2") (pin "61") (pinfunction "EEDATA_61") (pintype "bidirectional"))
      (node (ref "R6") (pin "2") (pinfunction "2_2") (pintype "passive"))
      (node (ref "U7") (pin "3") (pinfunction "D_3") (pintype "input"))
    )
    (net (code "19") (name "Net-(IC2-REF)") (class "Default")
      (node (ref "IC2") (pin "6") (pinfunction "REF_6") (pintype "bidirectional"))
      (node (ref "R1") (pin "2") (pinfunction "2_2") (pintype "passive"))
    )
    (net (code "20") (name "Net-(IC2-RESET#)") (class "Default")
      (node (ref "IC2") (pin "14") (pinfunction "RESET#_14") (pintype "bidirectional"))
      (node (ref "R2") (pin "1") (pinfunction "1_1") (pintype "passive"))
    )
    (net (code "21") (name "Net-(IC2-VPHY)") (class "Default")
      (node (ref "C24") (pin "1") (pinfunction "1_1") (pintype "passive"))
      (node (ref "C26") (pin "1") (pinfunction "1_1") (pintype "passive"))
      (node (ref "IC2") (pin "4") (pinfunction "VPHY_4") (pintype "bidirectional"))
      (node (ref "L4") (pin "1") (pinfunction "1_1") (pintype "passive"))
    )
    (net (code "22") (name "Net-(IC2-VPLL)") (class "Default")
      (node (ref "C23") (pin "1") (pinfunction "1_1") (pintype "passive"))
      (node (ref "C25") (pin "1") (pinfunction "1_1") (pintype "passive"))
      (node (ref "IC2") (pin "9") (pinfunction "VPLL_9") (pintype "bidirectional"))
      (node (ref "L3") (pin "1") (pinfunction "1_1") (pintype "passive"))
    )
    (net (code "23") (name "Net-(U$2-IN+)") (class "Default")
      (node (ref "C3") (pin "1") (pinfunction "1_1") (pintype "passive"))
      (node (ref "R100") (pin "1") (pinfunction "1_1") (pintype "passive"))
      (node (ref "U$2") (pin "P$4") (pinfunction "IN+_P$4") (pintype "bidirectional"))
    )
    (net (code "24") (name "Net-(U1C-IO_L40N_2)") (class "Default")
      (node (ref "TP1") (pin "TP") (pinfunction "TP_TP") (pintype "input"))
      (node (ref "U1") (pin "P65") (pinfunction "IO_L40N_2_P65") (pintype "bidirectional"))
    )
    (net (code "25") (name "Net-(U1C-IO_L40P_2VREF_2)") (class "Default")
      (node (ref "TP4") (pin "TP") (pinfunction "TP_TP") (pintype "input"))
      (node (ref "U1") (pin "P64") (pinfunction "IO_L40P_2VREF_2_P64") (pintype "bidirectional"))
    )
    (net (code "26") (name "Net-(U1D-IO_L40N_3VREF_3)") (class "Default")
      (node (ref "TP2") (pin "TP") (pinfunction "TP_TP") (pintype "input"))
      (node (ref "U1") (pin "P63") (pinfunction "IO_L40N_3VREF_3_P63") (pintype "bidirectional"))
    )
    (net (code "27") (name "Net-(U1D-IO_L40P_3)") (class "Default")
      (node (ref "TP3") (pin "TP") (pinfunction "TP_TP") (pintype "input"))
      (node (ref "U1") (pin "P62") (pinfunction "IO_L40P_3_P62") (pintype "bidirectional"))
    )
    (net (code "28") (name "Net-(U2--IN)") (class "Default")
      (node (ref "R100") (pin "2") (pinfunction "2_2") (pintype "passive"))
      (node (ref "U2") (pin "1") (pinfunction "OUT_1") (pintype "output"))
      (node (ref "U2") (pin "4") (pinfunction "-IN_4") (pintype "input"))
    )
    (net (code "29") (name "Net-(U7-Q)") (class "Default")
      (node (ref "R5") (pin "1") (pinfunction "1_1") (pintype "passive"))
      (node (ref "R6") (pin "1") (pinfunction "1_1") (pintype "passive"))
      (node (ref "U7") (pin "4") (pinfunction "Q_4") (pintype "output"))
    )
    (net (code "30") (name "OS") (class "Default")
      (node (ref "U$1") (pin "P$21") (pinfunction "OS_P$21") (pintype "bidirectional"))
      (node (ref "U2") (pin "3") (pinfunction "+IN_3") (pintype "input"))
    )
    (net (code "31") (name "OSC") (class "Default")
      (node (ref "Q1") (pin "3") (pinfunction "FO_3") (pintype "output"))
      (node (ref "U1") (pin "P39") (pinfunction "IO_L32N_4GCLK1_P39") (pintype "bidirectional"))
    )
    (net (code "32") (name "OSCI") (class "Default")
      (node (ref "IC2") (pin "2") (pinfunction "OSCI_2") (pintype "bidirectional"))
    )
    (net (code "33") (name "PROG_B") (class "Default")
      (node (ref "R19") (pin "2") (pinfunction "2_2") (pintype "passive"))
      (node (ref "U1") (pin "P99") (pinfunction "PROG_B_P99") (pintype "bidirectional"))
      (node (ref "U8") (pin "7") (pinfunction "~{CF}_7") (pintype "bidirectional"))
    )
    (net (code "34") (name "REF3V") (class "Default")
      (node (ref "C6") (pin "1") (pinfunction "1_1") (pintype "passive"))
      (node (ref "C7") (pin "1") (pinfunction "1_1") (pintype "passive"))
      (node (ref "U$2") (pin "P$7") (pinfunction "REF1_P$7") (pintype "bidirectional"))
      (node (ref "U$2") (pin "P$8") (pinfunction "REF2_P$8") (pintype "bidirectional"))
      (node (ref "U6") (pin "5") (pinfunction "VOUT_SENSE_5") (pintype "output"))
      (node (ref "U6") (pin "6") (pinfunction "VOUT_FORCE_6") (pintype "output"))
    )
    (net (code "35") (name "SCK") (class "Default")
      (node (ref "U$2") (pin "P$13") (pinfunction "SCK_P$13") (pintype "bidirectional"))
      (node (ref "U1") (pin "P97") (pinfunction "IO_L01N_0VRP_0_P97") (pintype "bidirectional"))
    )
    (net (code "36") (name "SDO") (class "Default")
      (node (ref "U$2") (pin "P$14") (pinfunction "SDO_P$14") (pintype "bidirectional"))
      (node (ref "U1") (pin "P96") (pinfunction "IO_L01P_0VRN_0_P96") (pintype "bidirectional"))
    )
    (net (code "37") (name "SH") (class "Default")
      (node (ref "U$1") (pin "P$5") (pinfunction "SH_P$5") (pintype "bidirectional"))
      (node (ref "U1") (pin "P16") (pinfunction "IO_L24N_6VREF_6_P16") (pintype "bidirectional"))
    )
    (net (code "38") (name "TCK") (class "Default")
      (node (ref "JTAG") (pin "7") (pinfunction "7_7") (pintype "passive"))
      (node (ref "U1") (pin "P77") (pinfunction "TCK_P77") (pintype "bidirectional"))
      (node (ref "U8") (pin "6") (pinfunction "TCK_6") (pintype "input"))
    )
    (net (code "39") (name "TD0") (class "Default")
      (node (ref "JTAG") (pin "5") (pinfunction "5_5") (pintype "passive"))
    )
    (net (code "40") (name "TDI") (class "Default")
      (node (ref "JTAG") (pin "9") (pinfunction "9_9") (pintype "passive"))
      (node (ref "U8") (pin "4") (pinfunction "TDI_4") (pintype "input"))
    )
    (net (code "41") (name "TDO") (class "Default")
      (node (ref "U1") (pin "P76") (pinfunction "TDO_P76") (pintype "bidirectional"))
    )
    (net (code "42") (name "TDOE") (class "Default")
      (node (ref "U1") (pin "P100") (pinfunction "TDI_P100") (pintype "bidirectional"))
      (node (ref "U8") (pin "17") (pinfunction "TDO_17") (pintype "output"))
    )
    (net (code "43") (name "TMS") (class "Default")
      (node (ref "JTAG") (pin "3") (pinfunction "3_3") (pintype "passive"))
      (node (ref "U1") (pin "P78") (pinfunction "TMS_P78") (pintype "bidirectional"))
      (node (ref "U8") (pin "5") (pinfunction "TMS_5") (pintype "input"))
    )
    (net (code "44") (name "VCC5") (class "Default")
      (node (ref "C1") (pin "1") (pinfunction "1_1") (pintype "passive"))
      (node (ref "C17") (pin "1") (pinfunction "1_1") (pintype "passive"))
      (node (ref "C48") (pin "1") (pinfunction "1_1") (pintype "passive"))
      (node (ref "C51") (pin "1") (pinfunction "1_1") (pintype "passive"))
      (node (ref "IC4") (pin "1") (pinfunction "VI_1") (pintype "input"))
      (node (ref "IC6") (pin "1") (pinfunction "VI_1") (pintype "input"))
      (node (ref "U$1") (pin "P$1") (pinfunction "VDD_P$1") (pintype "bidirectional"))
      (node (ref "U$1") (pin "P$2") (pinfunction "VAD_P$2") (pintype "bidirectional"))
      (node (ref "X1") (pin "1") (pinfunction "1_1") (pintype "passive"))
    )
    (net (code "45") (name "VCC12") (class "Default")
      (node (ref "C56") (pin "1") (pinfunction "1_1") (pintype "passive"))
      (node (ref "C61") (pin "1") (pinfunction "1_1") (pintype "passive"))
      (node (ref "C62") (pin "1") (pinfunction "1_1") (pintype "passive"))
      (node (ref "C63") (pin "1") (pinfunction "1_1") (pintype "passive"))
      (node (ref "C64") (pin "1") (pinfunction "1_1") (pintype "passive"))
      (node (ref "IC3") (pin "3") (pinfunction "VO_3") (pintype "passive"))
      (node (ref "U1") (pin "P18") (pinfunction "VCCINT0_P18") (pintype "passive"))
      (node (ref "U1") (pin "P45") (pinfunction "VCCINT1_P45") (pintype "passive"))
      (node (ref "U1") (pin "P69") (pinfunction "VCCINT2_P69") (pintype "passive"))
      (node (ref "U1") (pin "P93") (pinfunction "VCCINT3_P93") (pintype "passive"))
    )
    (net (code "46") (name "VCC18") (class "Default")
      (node (ref "C10") (pin "1") (pinfunction "1_1") (pintype "passive"))
      (node (ref "C11") (pin "1") (pinfunction "1_1") (pintype "passive"))
      (node (ref "C14") (pin "1") (pinfunction "1_1") (pintype "passive"))
      (node (ref "IC2") (pin "12") (pinfunction "VCORE0_12") (pintype "bidirectional"))
      (node (ref "IC2") (pin "37") (pinfunction "VCORE1_37") (pintype "bidirectional"))
      (node (ref "IC2") (pin "49") (pinfunction "VREGOUT_49") (pintype "bidirectional"))
      (node (ref "IC2") (pin "64") (pinfunction "VCORE2_64") (pintype "bidirectional"))
    )
    (net (code "47") (name "VCC25") (class "Default")
      (node (ref "C20") (pin "1") (pinfunction "1_1") (pintype "passive"))
      (node (ref "C52") (pin "1") (pinfunction "1_1") (pintype "passive"))
      (node (ref "C58") (pin "1") (pinfunction "1_1") (pintype "passive"))
      (node (ref "C59") (pin "1") (pinfunction "1_1") (pintype "passive"))
      (node (ref "C60") (pin "1") (pinfunction "1_1") (pintype "passive"))
      (node (ref "C8") (pin "1") (pinfunction "1_1") (pintype "passive"))
      (node (ref "C82") (pin "1") (pinfunction "1_1") (pintype "passive"))
      (node (ref "C83") (pin "1") (pinfunction "1_1") (pintype "passive"))
      (node (ref "C84") (pin "1") (pinfunction "1_1") (pintype "passive"))
      (node (ref "C85") (pin "1") (pinfunction "1_1") (pintype "passive"))
      (node (ref "IC4") (pin "3") (pinfunction "VO_3") (pintype "passive"))
      (node (ref "JTAG") (pin "1") (pinfunction "1_1") (pintype "passive"))
      (node (ref "R19") (pin "1") (pinfunction "1_1") (pintype "passive"))
      (node (ref "R20") (pin "2") (pinfunction "2_2") (pintype "passive"))
      (node (ref "R21") (pin "1") (pinfunction "1_1") (pintype "passive"))
      (node (ref "U$2") (pin "P$2") (pinfunction "VDD_P$2") (pintype "bidirectional"))
      (node (ref "U1") (pin "P24") (pinfunction "M1_P24") (pintype "bidirectional"))
      (node (ref "U1") (pin "P25") (pinfunction "M0_P25") (pintype "bidirectional"))
      (node (ref "U1") (pin "P26") (pinfunction "M2_P26") (pintype "bidirectional"))
      (node (ref "U1") (pin "P33") (pinfunction "VCCAUX1_P33") (pintype "passive"))
      (node (ref "U1") (pin "P58") (pinfunction "VCCAUX2_P58") (pintype "passive"))
      (node (ref "U1") (pin "P7") (pinfunction "VCCAUX0_P7") (pintype "passive"))
      (node (ref "U1") (pin "P84") (pinfunction "VCCAUX3_P84") (pintype "passive"))
      (node (ref "U8") (pin "19") (pinfunction "VCCO_19") (pintype "power_in"))
      (node (ref "U8") (pin "20") (pinfunction "VCCJ_20") (pintype "power_in"))
    )
    (net (code "48") (name "VCC33") (class "Default")
      (node (ref "C12") (pin "1") (pinfunction "1_1") (pintype "passive"))
      (node (ref "C13") (pin "1") (pinfunction "1_1") (pintype "passive"))
      (node (ref "C15") (pin "1") (pinfunction "1_1") (pintype "passive"))
      (node (ref "C16") (pin "1") (pinfunction "1_1") (pintype "passive"))
      (node (ref "C19") (pin "1") (pinfunction "1_1") (pintype "passive"))
      (node (ref "C2") (pin "1") (pinfunction "1_1") (pintype "passive"))
      (node (ref "C21") (pin "1") (pinfunction "1_1") (pintype "passive"))
      (node (ref "C22") (pin "1") (pinfunction "1_1") (pintype "passive"))
      (node (ref "C4") (pin "1") (pinfunction "1_1") (pintype "passive"))
      (node (ref "C5") (pin "1") (pinfunction "1_1") (pintype "passive"))
      (node (ref "C55") (pin "1") (pinfunction "1_1") (pintype "passive"))
      (node (ref "C70") (pin "1") (pinfunction "1_1") (pintype "passive"))
      (node (ref "C72") (pin "1") (pinfunction "1_1") (pintype "passive"))
      (node (ref "C73") (pin "1") (pinfunction "1_1") (pintype "passive"))
      (node (ref "C74") (pin "1") (pinfunction "1_1") (pintype "passive"))
      (node (ref "C76") (pin "1") (pinfunction "1_1") (pintype "passive"))
      (node (ref "C78") (pin "1") (pinfunction "1_1") (pintype "passive"))
      (node (ref "C79") (pin "1") (pinfunction "1_1") (pintype "passive"))
      (node (ref "C81") (pin "1") (pinfunction "1_1") (pintype "passive"))
      (node (ref "C9") (pin "1") (pinfunction "1_1") (pintype "passive"))
      (node (ref "IC2") (pin "20") (pinfunction "VCCIO0_20") (pintype "bidirectional"))
      (node (ref "IC2") (pin "31") (pinfunction "VCCIO1_31") (pintype "bidirectional"))
      (node (ref "IC2") (pin "42") (pinfunction "VCCIO2_42") (pintype "bidirectional"))
      (node (ref "IC2") (pin "50") (pinfunction "VREGIN_50") (pintype "bidirectional"))
      (node (ref "IC2") (pin "56") (pinfunction "VCCIO3_56") (pintype "bidirectional"))
      (node (ref "IC3") (pin "1") (pinfunction "VI_1") (pintype "input"))
      (node (ref "IC6") (pin "3") (pinfunction "VO_3") (pintype "passive"))
      (node (ref "L3") (pin "2") (pinfunction "2_2") (pintype "passive"))
      (node (ref "L4") (pin "2") (pinfunction "2_2") (pintype "passive"))
      (node (ref "Q1") (pin "4") (pinfunction "VCC_4") (pintype "power_in"))
      (node (ref "R2") (pin "2") (pinfunction "2_2") (pintype "passive"))
      (node (ref "R3") (pin "2") (pinfunction "2_2") (pintype "passive"))
      (node (ref "R4") (pin "2") (pinfunction "2_2") (pintype "passive"))
      (node (ref "R5") (pin "2") (pinfunction "2_2") (pintype "passive"))
      (node (ref "U$2") (pin "P$15") (pinfunction "OVDD_P$15") (pintype "bidirectional"))
      (node (ref "U1") (pin "P19") (pinfunction "VCCO_6_P19") (pintype "passive"))
      (node (ref "U1") (pin "P31") (pinfunction "VCCO_5_P31") (pintype "passive"))
      (node (ref "U1") (pin "P57") (pinfunction "VCCO_3_P57") (pintype "passive"))
      (node (ref "U1") (pin "P6") (pinfunction "VCCO_7_P6") (pintype "passive"))
      (node (ref "U1") (pin "P70") (pinfunction "VCCO_2_P70") (pintype "passive"))
      (node (ref "U1") (pin "P83") (pinfunction "VCCO_1_P83") (pintype "passive"))
      (node (ref "U1") (pin "P94") (pinfunction "VCCO_0_P94") (pintype "passive"))
      (node (ref "U2") (pin "5") (pinfunction "V+_5") (pintype "power_in"))
      (node (ref "U6") (pin "3") (pinfunction "ENABLE_3") (pintype "input"))
      (node (ref "U6") (pin "4") (pinfunction "VIN_4") (pintype "input"))
      (node (ref "U7") (pin "6") (pinfunction "ORG_6") (pintype "input"))
      (node (ref "U7") (pin "8") (pinfunction "VCC_8") (pintype "power_in"))
      (node (ref "U8") (pin "18") (pinfunction "VCCINT_18") (pintype "power_in"))
    )
    (net (code "49") (name "unconnected-(IC2-ACBUS0{slash}TXDEN{slash}GPIOH0-Pad26)") (class "Default")
      (node (ref "IC2") (pin "26") (pinfunction "ACBUS0/TXDEN/GPIOH0_26") (pintype "bidirectional"))
    )
    (net (code "50") (name "unconnected-(IC2-ACBUS1{slash}GPIOH1-Pad27)") (class "Default")
      (node (ref "IC2") (pin "27") (pinfunction "ACBUS1/GPIOH1_27") (pintype "bidirectional"))
    )
    (net (code "51") (name "unconnected-(IC2-ACBUS2{slash}GPIOH2-Pad28)") (class "Default")
      (node (ref "IC2") (pin "28") (pinfunction "ACBUS2/GPIOH2_28") (pintype "bidirectional"))
    )
    (net (code "52") (name "unconnected-(IC2-ACBUS3{slash}RXLED#{slash}GPIOH3-Pad29)") (class "Default")
      (node (ref "IC2") (pin "29") (pinfunction "ACBUS3/RXLED#/GPIOH3_29") (pintype "bidirectional"))
    )
    (net (code "53") (name "unconnected-(IC2-ACBUS4{slash}TXLED#{slash}GPIOH4-Pad30)") (class "Default")
      (node (ref "IC2") (pin "30") (pinfunction "ACBUS4/TXLED#/GPIOH4_30") (pintype "bidirectional"))
    )
    (net (code "54") (name "unconnected-(IC2-ACBUS5{slash}GPIOH5-Pad32)") (class "Default")
      (node (ref "IC2") (pin "32") (pinfunction "ACBUS5/GPIOH5_32") (pintype "bidirectional"))
    )
    (net (code "55") (name "unconnected-(IC2-ACBUS6{slash}GPIOH6-Pad33)") (class "Default")
      (node (ref "IC2") (pin "33") (pinfunction "ACBUS6/GPIOH6_33") (pintype "bidirectional"))
    )
    (net (code "56") (name "unconnected-(IC2-ACBUS7{slash}GPIOH7-Pad34)") (class "Default")
      (node (ref "IC2") (pin "34") (pinfunction "ACBUS7/GPIOH7_34") (pintype "bidirectional"))
    )
    (net (code "57") (name "unconnected-(IC2-ADBUS0{slash}TXD{slash}TCK{slash}SK-Pad16)") (class "Default")
      (node (ref "IC2") (pin "16") (pinfunction "ADBUS0/TXD/TCK/SK_16") (pintype "bidirectional"))
    )
    (net (code "58") (name "unconnected-(IC2-ADBUS1{slash}RXD{slash}TDI{slash}DO-Pad17)") (class "Default")
      (node (ref "IC2") (pin "17") (pinfunction "ADBUS1/RXD/TDI/DO_17") (pintype "bidirectional"))
    )
    (net (code "59") (name "unconnected-(IC2-ADBUS2{slash}RTS#{slash}TDO{slash}DI-Pad18)") (class "Default")
      (node (ref "IC2") (pin "18") (pinfunction "ADBUS2/RTS#/TDO/DI_18") (pintype "bidirectional"))
    )
    (net (code "60") (name "unconnected-(IC2-ADBUS3{slash}CTS#{slash}TMS{slash}CS-Pad19)") (class "Default")
      (node (ref "IC2") (pin "19") (pinfunction "ADBUS3/CTS#/TMS/CS_19") (pintype "bidirectional"))
    )
    (net (code "61") (name "unconnected-(IC2-ADBUS4{slash}DTR#{slash}GPIOL0-Pad21)") (class "Default")
      (node (ref "IC2") (pin "21") (pinfunction "ADBUS4/DTR#/GPIOL0_21") (pintype "bidirectional"))
    )
    (net (code "62") (name "unconnected-(IC2-ADBUS5{slash}DSR#{slash}GPIOL1-Pad22)") (class "Default")
      (node (ref "IC2") (pin "22") (pinfunction "ADBUS5/DSR#/GPIOL1_22") (pintype "bidirectional"))
    )
    (net (code "63") (name "unconnected-(IC2-ADBUS6{slash}DCD#{slash}GPIOL2-Pad23)") (class "Default")
      (node (ref "IC2") (pin "23") (pinfunction "ADBUS6/DCD#/GPIOL2_23") (pintype "bidirectional"))
    )
    (net (code "64") (name "unconnected-(IC2-ADBUS7{slash}RI#{slash}GPIOL3-Pad24)") (class "Default")
      (node (ref "IC2") (pin "24") (pinfunction "ADBUS7/RI#/GPIOL3_24") (pintype "bidirectional"))
    )
    (net (code "65") (name "unconnected-(IC2-BCBUS0{slash}GPIOH1-Pad48)") (class "Default")
      (node (ref "IC2") (pin "48") (pinfunction "BCBUS0/GPIOH1_48") (pintype "bidirectional"))
    )
    (net (code "66") (name "unconnected-(IC2-BCBUS1{slash}GPIOH2-Pad52)") (class "Default")
      (node (ref "IC2") (pin "52") (pinfunction "BCBUS1/GPIOH2_52") (pintype "bidirectional"))
    )
    (net (code "67") (name "unconnected-(IC2-BCBUS2-Pad53)") (class "Default")
      (node (ref "IC2") (pin "53") (pinfunction "BCBUS2_53") (pintype "bidirectional"))
    )
    (net (code "68") (name "unconnected-(IC2-BCBUS3{slash}RXLED#{slash}GPIOH3-Pad54)") (class "Default")
      (node (ref "IC2") (pin "54") (pinfunction "BCBUS3/RXLED#/GPIOH3_54") (pintype "bidirectional"))
    )
    (net (code "69") (name "unconnected-(IC2-BCBUS4{slash}TXLED#{slash}GPIOH4-Pad55)") (class "Default")
      (node (ref "IC2") (pin "55") (pinfunction "BCBUS4/TXLED#/GPIOH4_55") (pintype "bidirectional"))
    )
    (net (code "70") (name "unconnected-(IC2-BCBUS5{slash}GPIOH5-Pad57)") (class "Default")
      (node (ref "IC2") (pin "57") (pinfunction "BCBUS5/GPIOH5_57") (pintype "bidirectional"))
    )
    (net (code "71") (name "unconnected-(IC2-BCBUS6{slash}GPIOH6-Pad58)") (class "Default")
      (node (ref "IC2") (pin "58") (pinfunction "BCBUS6/GPIOH6_58") (pintype "bidirectional"))
    )
    (net (code "72") (name "unconnected-(IC2-BCBUS7{slash}GPIOH7-Pad59)") (class "Default")
      (node (ref "IC2") (pin "59") (pinfunction "BCBUS7/GPIOH7_59") (pintype "bidirectional"))
    )
    (net (code "73") (name "unconnected-(IC2-BDBUS4{slash}DTR#{slash}GPIOL0-Pad43)") (class "Default")
      (node (ref "IC2") (pin "43") (pinfunction "BDBUS4/DTR#/GPIOL0_43") (pintype "bidirectional"))
    )
    (net (code "74") (name "unconnected-(IC2-BDBUS5{slash}DSR#{slash}GPIOL1-Pad44)") (class "Default")
      (node (ref "IC2") (pin "44") (pinfunction "BDBUS5/DSR#/GPIOL1_44") (pintype "bidirectional"))
    )
    (net (code "75") (name "unconnected-(IC2-BDBUS6{slash}DCD#{slash}GPIOL2-Pad45)") (class "Default")
      (node (ref "IC2") (pin "45") (pinfunction "BDBUS6/DCD#/GPIOL2_45") (pintype "bidirectional"))
    )
    (net (code "76") (name "unconnected-(IC2-BDBUS7{slash}RI#{slash}GPIOL3-Pad46)") (class "Default")
      (node (ref "IC2") (pin "46") (pinfunction "BDBUS7/RI#/GPIOL3_46") (pintype "bidirectional"))
    )
    (net (code "77") (name "unconnected-(IC2-OSC0-Pad3)") (class "Default")
      (node (ref "IC2") (pin "3") (pinfunction "OSC0_3") (pintype "bidirectional"))
    )
    (net (code "78") (name "unconnected-(IC2-PWREN#-Pad60)") (class "Default")
      (node (ref "IC2") (pin "60") (pinfunction "PWREN#_60") (pintype "bidirectional"))
    )
    (net (code "79") (name "unconnected-(IC2-SUSPEND#-Pad36)") (class "Default")
      (node (ref "IC2") (pin "36") (pinfunction "SUSPEND#_36") (pintype "bidirectional"))
    )
    (net (code "80") (name "unconnected-(Q1-OE-Pad1)") (class "Default")
      (node (ref "Q1") (pin "1") (pinfunction "OE_1") (pintype "input"))
    )
    (net (code "81") (name "unconnected-(U1A-IO_L31N_0-PadP92)") (class "Default")
      (node (ref "U1") (pin "P92") (pinfunction "IO_L31N_0_P92") (pintype "bidirectional"))
    )
    (net (code "82") (name "unconnected-(U1A-IO_L31P_0VREF_0-PadP91)") (class "Default")
      (node (ref "U1") (pin "P91") (pinfunction "IO_L31P_0VREF_0_P91") (pintype "bidirectional"))
    )
    (net (code "83") (name "unconnected-(U1A-IO_L32N_0GCLK7-PadP90)") (class "Default")
      (node (ref "U1") (pin "P90") (pinfunction "IO_L32N_0GCLK7_P90") (pintype "bidirectional"))
    )
    (net (code "84") (name "unconnected-(U1A-IO_L32P_0GCLK6-PadP89)") (class "Default")
      (node (ref "U1") (pin "P89") (pinfunction "IO_L32P_0GCLK6_P89") (pintype "bidirectional"))
    )
    (net (code "85") (name "unconnected-(U1B-IO-PadP81)") (class "Default")
      (node (ref "U1") (pin "P81") (pinfunction "IO_P81") (pintype "bidirectional"))
    )
    (net (code "86") (name "unconnected-(U1B-IO_L01N_1VRP_1-PadP80)") (class "Default")
      (node (ref "U1") (pin "P80") (pinfunction "IO_L01N_1VRP_1_P80") (pintype "bidirectional"))
    )
    (net (code "87") (name "unconnected-(U1B-IO_L01P_1VRN_1-PadP79)") (class "Default")
      (node (ref "U1") (pin "P79") (pinfunction "IO_L01P_1VRN_1_P79") (pintype "bidirectional"))
    )
    (net (code "88") (name "unconnected-(U1C-IO_L01N_2VRP_2-PadP75)") (class "Default")
      (node (ref "U1") (pin "P75") (pinfunction "IO_L01N_2VRP_2_P75") (pintype "bidirectional"))
    )
    (net (code "89") (name "unconnected-(U1C-IO_L01P_2VRN_2-PadP74)") (class "Default")
      (node (ref "U1") (pin "P74") (pinfunction "IO_L01P_2VRN_2_P74") (pintype "bidirectional"))
    )
    (net (code "90") (name "unconnected-(U1C-IO_L21N_2-PadP72)") (class "Default")
      (node (ref "U1") (pin "P72") (pinfunction "IO_L21N_2_P72") (pintype "bidirectional"))
    )
    (net (code "91") (name "unconnected-(U1C-IO_L21P_2-PadP71)") (class "Default")
      (node (ref "U1") (pin "P71") (pinfunction "IO_L21P_2_P71") (pintype "bidirectional"))
    )
    (net (code "92") (name "unconnected-(U1C-IO_L24N_2-PadP68)") (class "Default")
      (node (ref "U1") (pin "P68") (pinfunction "IO_L24N_2_P68") (pintype "bidirectional"))
    )
    (net (code "93") (name "unconnected-(U1C-IO_L24P_2-PadP67)") (class "Default")
      (node (ref "U1") (pin "P67") (pinfunction "IO_L24P_2_P67") (pintype "bidirectional"))
    )
    (net (code "94") (name "unconnected-(U1D-IO0-PadP55)") (class "Default")
      (node (ref "U1") (pin "P55") (pinfunction "IO0_P55") (pintype "bidirectional"))
    )
    (net (code "95") (name "unconnected-(U1D-IO1-PadP59)") (class "Default")
      (node (ref "U1") (pin "P59") (pinfunction "IO1_P59") (pintype "bidirectional"))
    )
    (net (code "96") (name "unconnected-(U1D-IO_L01N_3VRP_3-PadP54)") (class "Default")
      (node (ref "U1") (pin "P54") (pinfunction "IO_L01N_3VRP_3_P54") (pintype "bidirectional"))
    )
    (net (code "97") (name "unconnected-(U1D-IO_L01P_3VRN_3-PadP53)") (class "Default")
      (node (ref "U1") (pin "P53") (pinfunction "IO_L01P_3VRN_3_P53") (pintype "bidirectional"))
    )
    (net (code "98") (name "unconnected-(U1D-IO_L24N_3-PadP61)") (class "Default")
      (node (ref "U1") (pin "P61") (pinfunction "IO_L24N_3_P61") (pintype "bidirectional"))
    )
    (net (code "99") (name "unconnected-(U1D-IO_L24P_3-PadP60)") (class "Default")
      (node (ref "U1") (pin "P60") (pinfunction "IO_L24P_3_P60") (pintype "bidirectional"))
    )
    (net (code "100") (name "unconnected-(U1E-IO_L01N_4VRP_4-PadP50)") (class "Default")
      (node (ref "U1") (pin "P50") (pinfunction "IO_L01N_4VRP_4_P50") (pintype "bidirectional"))
    )
    (net (code "101") (name "unconnected-(U1E-IO_L01P_4VRN_4-PadP49)") (class "Default")
      (node (ref "U1") (pin "P49") (pinfunction "IO_L01P_4VRN_4_P49") (pintype "bidirectional"))
    )
    (net (code "102") (name "unconnected-(U1E-IO_L27N_4DIND0-PadP48)") (class "Default")
      (node (ref "U1") (pin "P48") (pinfunction "IO_L27N_4DIND0_P48") (pintype "bidirectional"))
    )
    (net (code "103") (name "unconnected-(U1E-IO_L27P_4D1-PadP47)") (class "Default")
      (node (ref "U1") (pin "P47") (pinfunction "IO_L27P_4D1_P47") (pintype "bidirectional"))
    )
    (net (code "104") (name "unconnected-(U1E-IO_L30N_4D2-PadP44)") (class "Default")
      (node (ref "U1") (pin "P44") (pinfunction "IO_L30N_4D2_P44") (pintype "bidirectional"))
    )
    (net (code "105") (name "unconnected-(U1E-IO_L30P_4D3-PadP43)") (class "Default")
      (node (ref "U1") (pin "P43") (pinfunction "IO_L30P_4D3_P43") (pintype "bidirectional"))
    )
    (net (code "106") (name "unconnected-(U1E-IO_L31N_4INIT_B-PadP42)") (class "Default")
      (node (ref "U1") (pin "P42") (pinfunction "IO_L31N_4INIT_B_P42") (pintype "bidirectional"))
    )
    (net (code "107") (name "unconnected-(U1E-IO_L31P_4DOUTBUSY-PadP40)") (class "Default")
      (node (ref "U1") (pin "P40") (pinfunction "IO_L31P_4DOUTBUSY_P40") (pintype "bidirectional"))
    )
    (net (code "108") (name "unconnected-(U1E-IO_L32P_4GCLK0-PadP38)") (class "Default")
      (node (ref "U1") (pin "P38") (pinfunction "IO_L32P_4GCLK0_P38") (pintype "bidirectional"))
    )
    (net (code "109") (name "unconnected-(U1E-VCCO_4-PadP46)") (class "Default")
      (node (ref "U1") (pin "P46") (pinfunction "VCCO_4_P46") (pintype "passive"))
    )
    (net (code "110") (name "unconnected-(U1F-IO_L01N_5RDWR_B-PadP28)") (class "Default")
      (node (ref "U1") (pin "P28") (pinfunction "IO_L01N_5RDWR_B_P28") (pintype "bidirectional"))
    )
    (net (code "111") (name "unconnected-(U1F-IO_L01P_5CS_B-PadP27)") (class "Default")
      (node (ref "U1") (pin "P27") (pinfunction "IO_L01P_5CS_B_P27") (pintype "bidirectional"))
    )
    (net (code "112") (name "unconnected-(U1F-IO_L28N_5D6-PadP32)") (class "Default")
      (node (ref "U1") (pin "P32") (pinfunction "IO_L28N_5D6_P32") (pintype "bidirectional"))
    )
    (net (code "113") (name "unconnected-(U1F-IO_L28P_5D7-PadP30)") (class "Default")
      (node (ref "U1") (pin "P30") (pinfunction "IO_L28P_5D7_P30") (pintype "bidirectional"))
    )
    (net (code "114") (name "unconnected-(U1F-IO_L31N_5D4-PadP35)") (class "Default")
      (node (ref "U1") (pin "P35") (pinfunction "IO_L31N_5D4_P35") (pintype "bidirectional"))
    )
    (net (code "115") (name "unconnected-(U1F-IO_L31P_5D5-PadP34)") (class "Default")
      (node (ref "U1") (pin "P34") (pinfunction "IO_L31P_5D5_P34") (pintype "bidirectional"))
    )
    (net (code "116") (name "unconnected-(U1F-IO_L32N_5GCLK3-PadP37)") (class "Default")
      (node (ref "U1") (pin "P37") (pinfunction "IO_L32N_5GCLK3_P37") (pintype "bidirectional"))
    )
    (net (code "117") (name "unconnected-(U1F-IO_L32P_5GCLK2-PadP36)") (class "Default")
      (node (ref "U1") (pin "P36") (pinfunction "IO_L32P_5GCLK2_P36") (pintype "bidirectional"))
    )
    (net (code "118") (name "unconnected-(U1G-IO0-PadP17)") (class "Default")
      (node (ref "U1") (pin "P17") (pinfunction "IO0_P17") (pintype "bidirectional"))
    )
    (net (code "119") (name "unconnected-(U1G-IO1-PadP21)") (class "Default")
      (node (ref "U1") (pin "P21") (pinfunction "IO1_P21") (pintype "bidirectional"))
    )
    (net (code "120") (name "unconnected-(U1G-IO_L01N_6VRP_6-PadP23)") (class "Default")
      (node (ref "U1") (pin "P23") (pinfunction "IO_L01N_6VRP_6_P23") (pintype "bidirectional"))
    )
    (net (code "121") (name "unconnected-(U1G-IO_L01P_6VRN_6-PadP22)") (class "Default")
      (node (ref "U1") (pin "P22") (pinfunction "IO_L01P_6VRN_6_P22") (pintype "bidirectional"))
    )
    (net (code "122") (name "unconnected-(U1G-IO_L40P_6VREF_6-PadP13)") (class "Default")
      (node (ref "U1") (pin "P13") (pinfunction "IO_L40P_6VREF_6_P13") (pintype "bidirectional"))
    )
    (net (code "123") (name "unconnected-(U1H-IO_L01P_7VRN_7-PadP1)") (class "Default")
      (node (ref "U1") (pin "P1") (pinfunction "IO_L01P_7VRN_7_P1") (pintype "bidirectional"))
    )
    (net (code "124") (name "unconnected-(U1H-IO_L21N_7-PadP5)") (class "Default")
      (node (ref "U1") (pin "P5") (pinfunction "IO_L21N_7_P5") (pintype "bidirectional"))
    )
    (net (code "125") (name "unconnected-(U1H-IO_L23N_7-PadP9)") (class "Default")
      (node (ref "U1") (pin "P9") (pinfunction "IO_L23N_7_P9") (pintype "bidirectional"))
    )
    (net (code "126") (name "unconnected-(U1H-IO_L23P_7-PadP8)") (class "Default")
      (node (ref "U1") (pin "P8") (pinfunction "IO_L23P_7_P8") (pintype "bidirectional"))
    )
    (net (code "127") (name "unconnected-(U1H-IO_L40N_7VREF_7-PadP12)") (class "Default")
      (node (ref "U1") (pin "P12") (pinfunction "IO_L40N_7VREF_7_P12") (pintype "bidirectional"))
    )
    (net (code "128") (name "unconnected-(U1H-IO_L40P_7-PadP11)") (class "Default")
      (node (ref "U1") (pin "P11") (pinfunction "IO_L40P_7_P11") (pintype "bidirectional"))
    )
    (net (code "129") (name "unconnected-(U1J-HSWAP_EN-PadP98)") (class "Default")
      (node (ref "U1") (pin "P98") (pinfunction "HSWAP_EN_P98") (pintype "bidirectional"))
    )
    (net (code "130") (name "unconnected-(U8-(DNC)-Pad16)") (class "Default")
      (node (ref "U8") (pin "16") (pinfunction "(DNC)_16") (pintype "no_connect"))
    )
    (net (code "131") (name "unconnected-(U8-(DNC)_2-Pad12)") (class "Default")
      (node (ref "U8") (pin "12") (pinfunction "(DNC)_2_12") (pintype "no_connect"))
    )
    (net (code "132") (name "unconnected-(U8-(DNC)_3-Pad2)") (class "Default")
      (node (ref "U8") (pin "2") (pinfunction "(DNC)_3_2") (pintype "no_connect"))
    )
    (net (code "133") (name "unconnected-(U8-(DNC)_4-Pad15)") (class "Default")
      (node (ref "U8") (pin "15") (pinfunction "(DNC)_4_15") (pintype "no_connect"))
    )
    (net (code "134") (name "unconnected-(U8-(DNC)_5-Pad9)") (class "Default")
      (node (ref "U8") (pin "9") (pinfunction "(DNC)_5_9") (pintype "no_connect"))
    )
    (net (code "135") (name "unconnected-(U8-(DNC)_6-Pad14)") (class "Default")
      (node (ref "U8") (pin "14") (pinfunction "(DNC)_6_14") (pintype "no_connect"))
    )
    (net (code "136") (name "unconnected-(U8-~{CEO}-Pad13)") (class "Default")
      (node (ref "U8") (pin "13") (pinfunction "~{CEO}_13") (pintype "output"))
    )
  )
)
